# P2H-001.net
KiCad netlist of a schematic drawn in EAGLE
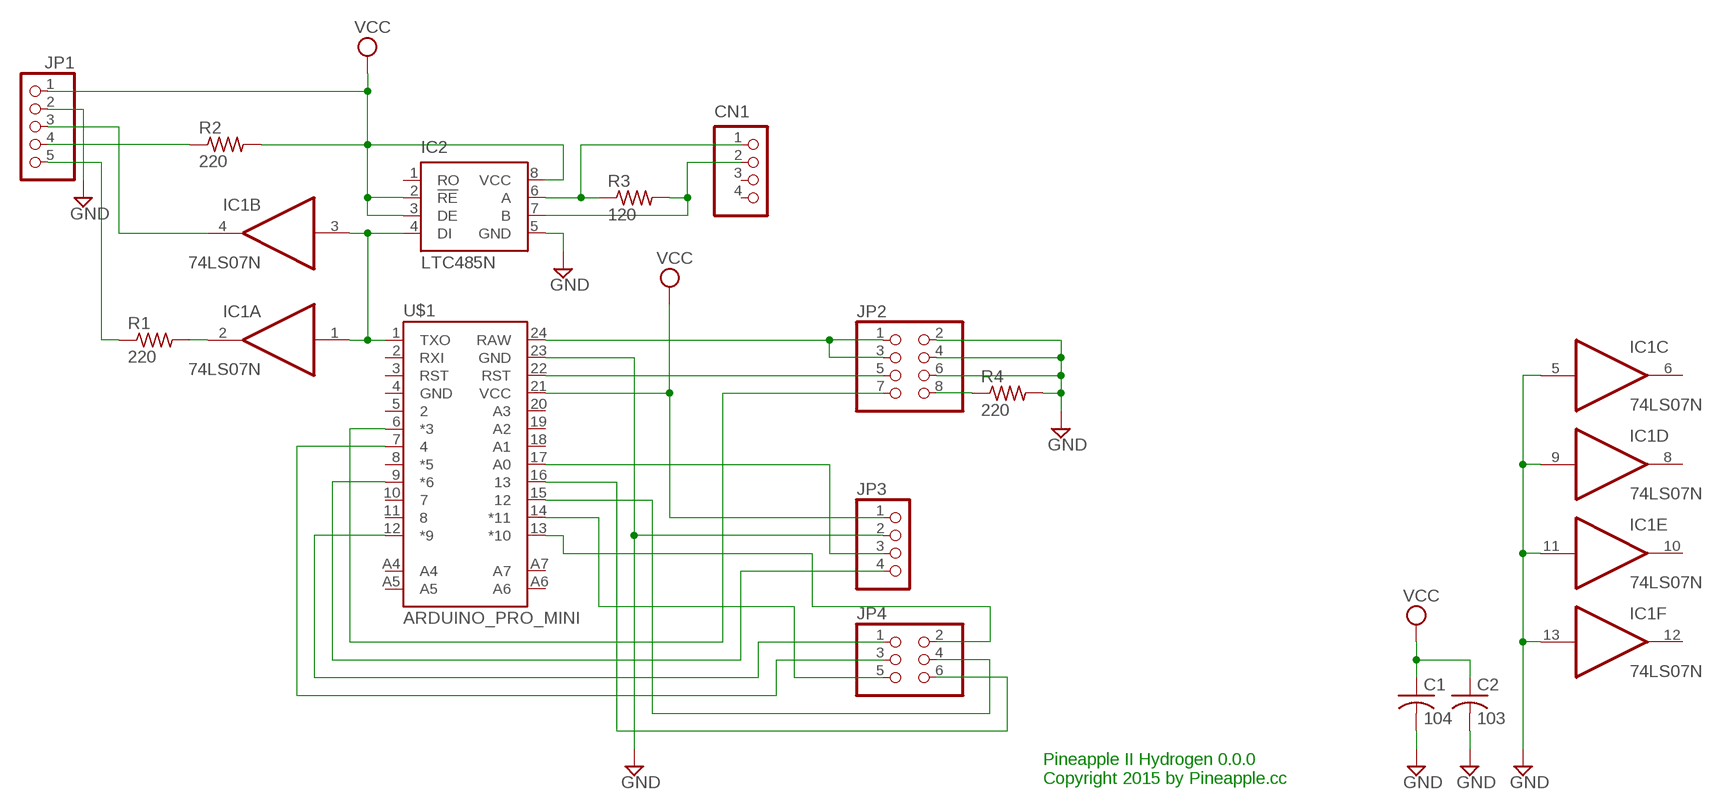
[diagram p0: schematic, sheet 1]

(export (version "E")
  (design (tool "Eeschema 10.0.6"))
  (components
    (comp (ref "C1")
      (value "104")
      (footprint "eagle-import:C025-025X050")
      (libsource (lib "eagle-import") (part "C-US025-025X050"))
    )
    (comp (ref "C2")
      (value "103")
      (footprint "eagle-import:C025-025X050")
      (libsource (lib "eagle-import") (part "C-US025-025X050"))
    )
    (comp (ref "CN1")
      (value "S4B-PH-K-S")
      (footprint "eagle-import:S4B-PH-K-S")
      (libsource (lib "eagle-import") (part "S4B-PH-K-S"))
    )
    (comp (ref "IC1")
      (value "74LS07N")
      (footprint "eagle-import:DIL14")
      (libsource (lib "eagle-import") (part "7407NLS"))
    )
    (comp (ref "IC2")
      (value "LTC485N")
      (footprint "eagle-import:DIL08")
      (libsource (lib "eagle-import") (part "LTC485N"))
    )
    (comp (ref "JP1")
      (value "PINHD-1X5")
      (footprint "eagle-import:1X05")
      (libsource (lib "eagle-import") (part "PINHD-1X5"))
    )
    (comp (ref "JP2")
      (value "PINHD-2X4")
      (footprint "eagle-import:2X04")
      (libsource (lib "eagle-import") (part "PINHD-2X4"))
    )
    (comp (ref "JP3")
      (value "PINHD-1X4")
      (footprint "eagle-import:1X04")
      (libsource (lib "eagle-import") (part "PINHD-1X4"))
    )
    (comp (ref "JP4")
      (value "PINHD-2X3")
      (footprint "eagle-import:2X03")
      (libsource (lib "eagle-import") (part "PINHD-2X3"))
    )
    (comp (ref "R1")
      (value "220")
      (footprint "eagle-import:0204_5")
      (libsource (lib "eagle-import") (part "R-US_0204/5"))
    )
    (comp (ref "R2")
      (value "220")
      (footprint "eagle-import:0204_5")
      (libsource (lib "eagle-import") (part "R-US_0204/5"))
    )
    (comp (ref "R3")
      (value "120")
      (footprint "eagle-import:0204_5")
      (libsource (lib "eagle-import") (part "R-US_0204/5"))
    )
    (comp (ref "R4")
      (value "220")
      (footprint "eagle-import:0204_5")
      (libsource (lib "eagle-import") (part "R-US_0204/5"))
    )
    (comp (ref "U$1")
      (value "ARDUINO_PRO_MINI")
      (footprint "eagle-import:ARDUINO_PRO_MINI")
      (libsource (lib "eagle-import") (part "ARDUINO_PRO_MINI"))
    )
  )
  (nets
    (net (code "1") (name "GND") (class "Default")
      (node (ref "C1") (pin "2") (pinfunction "2_2") (pintype "passive"))
      (node (ref "C2") (pin "2") (pinfunction "2_2") (pintype "passive"))
      (node (ref "IC1") (pin "11") (pinfunction "I_11") (pintype "input"))
      (node (ref "IC1") (pin "13") (pinfunction "I_13") (pintype "input"))
      (node (ref "IC1") (pin "5") (pinfunction "I_5") (pintype "input"))
      (node (ref "IC1") (pin "9") (pinfunction "I_9") (pintype "input"))
      (node (ref "IC2") (pin "5") (pinfunction "GND_5") (pintype "input"))
      (node (ref "JP1") (pin "2") (pinfunction "2_2") (pintype "passive"))
      (node (ref "JP2") (pin "2") (pinfunction "2_2") (pintype "passive"))
      (node (ref "JP2") (pin "4") (pinfunction "4_4") (pintype "passive"))
      (node (ref "JP2") (pin "6") (pinfunction "6_6") (pintype "passive"))
      (node (ref "JP3") (pin "2") (pinfunction "2_2") (pintype "passive"))
      (node (ref "R4") (pin "2") (pinfunction "2_2") (pintype "passive"))
      (node (ref "U$1") (pin "23") (pinfunction "GND_23") (pintype "bidirectional"))
    )
    (net (code "2") (name "Net-(IC1A-I)") (class "Default")
      (node (ref "IC1") (pin "1") (pinfunction "I_1") (pintype "input"))
      (node (ref "IC1") (pin "3") (pinfunction "I_3") (pintype "input"))
      (node (ref "IC2") (pin "4") (pinfunction "DI_4") (pintype "input"))
      (node (ref "U$1") (pin "1") (pinfunction "TXO_1") (pintype "bidirectional"))
    )
    (net (code "3") (name "Net-(IC1A-O)") (class "Default")
      (node (ref "IC1") (pin "2") (pinfunction "O_2") (pintype "open_collector"))
      (node (ref "R1") (pin "2") (pinfunction "2_2") (pintype "passive"))
    )
    (net (code "4") (name "Net-(IC1B-O)") (class "Default")
      (node (ref "IC1") (pin "4") (pinfunction "O_4") (pintype "open_collector"))
      (node (ref "JP1") (pin "3") (pinfunction "3_3") (pintype "passive"))
    )
    (net (code "5") (name "Net-(IC2-A)") (class "Default")
      (node (ref "CN1") (pin "1") (pinfunction "1_1") (pintype "passive"))
      (node (ref "IC2") (pin "6") (pinfunction "A_6") (pintype "bidirectional"))
      (node (ref "R3") (pin "1") (pinfunction "1_1") (pintype "passive"))
    )
    (net (code "6") (name "Net-(IC2-B)") (class "Default")
      (node (ref "CN1") (pin "2") (pinfunction "2_2") (pintype "passive"))
      (node (ref "IC2") (pin "7") (pinfunction "B_7") (pintype "bidirectional"))
      (node (ref "R3") (pin "2") (pinfunction "2_2") (pintype "passive"))
    )
    (net (code "7") (name "Net-(JP1-Pad4)") (class "Default")
      (node (ref "JP1") (pin "4") (pinfunction "4_4") (pintype "passive"))
      (node (ref "R2") (pin "1") (pinfunction "1_1") (pintype "passive"))
    )
    (net (code "8") (name "Net-(JP1-Pad5)") (class "Default")
      (node (ref "JP1") (pin "5") (pinfunction "5_5") (pintype "passive"))
      (node (ref "R1") (pin "1") (pinfunction "1_1") (pintype "passive"))
    )
    (net (code "9") (name "Net-(JP2-Pad5)") (class "Default")
      (node (ref "JP2") (pin "5") (pinfunction "5_5") (pintype "passive"))
      (node (ref "U$1") (pin "22") (pinfunction "RST_22") (pintype "bidirectional"))
    )
    (net (code "10") (name "Net-(JP2-Pad8)") (class "Default")
      (node (ref "JP2") (pin "8") (pinfunction "8_8") (pintype "passive"))
      (node (ref "R4") (pin "1") (pinfunction "1_1") (pintype "passive"))
    )
    (net (code "11") (name "Net-(U$1-*3)") (class "Default")
      (node (ref "JP2") (pin "7") (pinfunction "7_7") (pintype "passive"))
      (node (ref "U$1") (pin "6") (pinfunction "*3_6") (pintype "bidirectional"))
    )
    (net (code "12") (name "Net-(U$1-*6)") (class "Default")
      (node (ref "JP3") (pin "4") (pinfunction "4_4") (pintype "passive"))
      (node (ref "U$1") (pin "9") (pinfunction "*6_9") (pintype "bidirectional"))
    )
    (net (code "13") (name "Net-(U$1-*9)") (class "Default")
      (node (ref "JP4") (pin "1") (pinfunction "1_1") (pintype "passive"))
      (node (ref "U$1") (pin "12") (pinfunction "*9_12") (pintype "bidirectional"))
    )
    (net (code "14") (name "Net-(U$1-*10)") (class "Default")
      (node (ref "JP4") (pin "2") (pinfunction "2_2") (pintype "passive"))
      (node (ref "U$1") (pin "13") (pinfunction "*10_13") (pintype "bidirectional"))
    )
    (net (code "15") (name "Net-(U$1-*11)") (class "Default")
      (node (ref "JP4") (pin "5") (pinfunction "5_5") (pintype "passive"))
      (node (ref "U$1") (pin "14") (pinfunction "*11_14") (pintype "bidirectional"))
    )
    (net (code "16") (name "Net-(U$1-4)") (class "Default")
      (node (ref "JP4") (pin "3") (pinfunction "3_3") (pintype "passive"))
      (node (ref "U$1") (pin "7") (pinfunction "4_7") (pintype "bidirectional"))
    )
    (net (code "17") (name "Net-(U$1-12)") (class "Default")
      (node (ref "JP4") (pin "4") (pinfunction "4_4") (pintype "passive"))
      (node (ref "U$1") (pin "15") (pinfunction "12_15") (pintype "bidirectional"))
    )
    (net (code "18") (name "Net-(U$1-13)") (class "Default")
      (node (ref "JP4") (pin "6") (pinfunction "6_6") (pintype "passive"))
      (node (ref "U$1") (pin "16") (pinfunction "13_16") (pintype "bidirectional"))
    )
    (net (code "19") (name "Net-(U$1-A0)") (class "Default")
      (node (ref "JP3") (pin "3") (pinfunction "3_3") (pintype "passive"))
      (node (ref "U$1") (pin "17") (pinfunction "A0_17") (pintype "bidirectional"))
    )
    (net (code "20") (name "Net-(U$1-RAW)") (class "Default")
      (node (ref "JP2") (pin "1") (pinfunction "1_1") (pintype "passive"))
      (node (ref "JP2") (pin "3") (pinfunction "3_3") (pintype "passive"))
      (node (ref "U$1") (pin "24") (pinfunction "RAW_24") (pintype "bidirectional"))
    )
    (net (code "21") (name "VCC") (class "Default")
      (node (ref "C1") (pin "1") (pinfunction "1_1") (pintype "passive"))
      (node (ref "C2") (pin "1") (pinfunction "1_1") (pintype "passive"))
      (node (ref "IC2") (pin "2") (pinfunction "~{RE}_2") (pintype "input"))
      (node (ref "IC2") (pin "3") (pinfunction "DE_3") (pintype "input"))
      (node (ref "IC2") (pin "8") (pinfunction "VCC_8") (pintype "input"))
      (node (ref "JP1") (pin "1") (pinfunction "1_1") (pintype "passive"))
      (node (ref "JP3") (pin "1") (pinfunction "1_1") (pintype "passive"))
      (node (ref "R2") (pin "2") (pinfunction "2_2") (pintype "passive"))
      (node (ref "U$1") (pin "21") (pinfunction "VCC_21") (pintype "bidirectional"))
    )
    (net (code "22") (name "unconnected-(CN1-Pad3)") (class "Default")
      (node (ref "CN1") (pin "3") (pinfunction "3_3") (pintype "passive"))
    )
    (net (code "23") (name "unconnected-(CN1-Pad4)") (class "Default")
      (node (ref "CN1") (pin "4") (pinfunction "4_4") (pintype "passive"))
    )
    (net (code "24") (name "unconnected-(IC1C-O-Pad6)") (class "Default")
      (node (ref "IC1") (pin "6") (pinfunction "O_6") (pintype "open_collector"))
    )
    (net (code "25") (name "unconnected-(IC1D-O-Pad8)") (class "Default")
      (node (ref "IC1") (pin "8") (pinfunction "O_8") (pintype "open_collector"))
    )
    (net (code "26") (name "unconnected-(IC1E-O-Pad10)") (class "Default")
      (node (ref "IC1") (pin "10") (pinfunction "O_10") (pintype "open_collector"))
    )
    (net (code "27") (name "unconnected-(IC1F-O-Pad12)") (class "Default")
      (node (ref "IC1") (pin "12") (pinfunction "O_12") (pintype "open_collector"))
    )
    (net (code "28") (name "unconnected-(IC2-RO-Pad1)") (class "Default")
      (node (ref "IC2") (pin "1") (pinfunction "RO_1") (pintype "output"))
    )
    (net (code "29") (name "unconnected-(U$1-*5-Pad8)") (class "Default")
      (node (ref "U$1") (pin "8") (pinfunction "*5_8") (pintype "bidirectional"))
    )
    (net (code "30") (name "unconnected-(U$1-2-Pad5)") (class "Default")
      (node (ref "U$1") (pin "5") (pinfunction "2_5") (pintype "bidirectional"))
    )
    (net (code "31") (name "unconnected-(U$1-7-Pad10)") (class "Default")
      (node (ref "U$1") (pin "10") (pinfunction "7_10") (pintype "bidirectional"))
    )
    (net (code "32") (name "unconnected-(U$1-8-Pad11)") (class "Default")
      (node (ref "U$1") (pin "11") (pinfunction "8_11") (pintype "bidirectional"))
    )
    (net (code "33") (name "unconnected-(U$1-A1-Pad18)") (class "Default")
      (node (ref "U$1") (pin "18") (pinfunction "A1_18") (pintype "bidirectional"))
    )
    (net (code "34") (name "unconnected-(U$1-A2-Pad19)") (class "Default")
      (node (ref "U$1") (pin "19") (pinfunction "A2_19") (pintype "bidirectional"))
    )
    (net (code "35") (name "unconnected-(U$1-A3-Pad20)") (class "Default")
      (node (ref "U$1") (pin "20") (pinfunction "A3_20") (pintype "bidirectional"))
    )
    (net (code "36") (name "unconnected-(U$1-GND-Pad4)") (class "Default")
      (node (ref "U$1") (pin "4") (pinfunction "GND_4") (pintype "bidirectional"))
    )
    (net (code "37") (name "unconnected-(U$1-PadA4)") (class "Default")
      (node (ref "U$1") (pin "A4") (pinfunction "A4_A4") (pintype "bidirectional"))
    )
    (net (code "38") (name "unconnected-(U$1-PadA5)") (class "Default")
      (node (ref "U$1") (pin "A5") (pinfunction "A5_A5") (pintype "bidirectional"))
    )
    (net (code "39") (name "unconnected-(U$1-PadA6)") (class "Default")
      (node (ref "U$1") (pin "A6") (pinfunction "A6_A6") (pintype "bidirectional"))
    )
    (net (code "40") (name "unconnected-(U$1-PadA7)") (class "Default")
      (node (ref "U$1") (pin "A7") (pinfunction "A7_A7") (pintype "bidirectional"))
    )
    (net (code "41") (name "unconnected-(U$1-RST-Pad3)") (class "Default")
      (node (ref "U$1") (pin "3") (pinfunction "RST_3") (pintype "bidirectional"))
    )
    (net (code "42") (name "unconnected-(U$1-RXI-Pad2)") (class "Default")
      (node (ref "U$1") (pin "2") (pinfunction "RXI_2") (pintype "bidirectional"))
    )
  )
)
